# 12V_Supply.net
KiCad netlist of a schematic drawn in Altium Designer
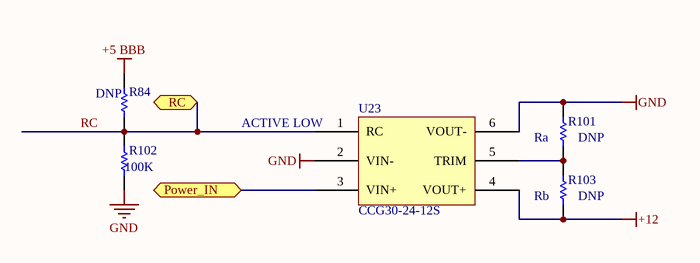
[diagram p0: 12V_Supply.SchDoc]

(export (version "E")
  (design (tool "Eeschema 10.0.6"))
  (components
    (comp (ref "R84")
      (value "DNP")
      (footprint "RESC0805(2012)_M")
      (description "RES SMD 100K OHM 1% 1/8W 0805")
      (fields
        (field (name "MANUFACTURER") "Vishay")
        (field (name "MANUFACTURER PART NUMBER") "CRCW0805100KFKEA")
      )
      (libsource (lib "Altium Content Vault") (part "CMP-1013-00017-1"))
    )
    (comp (ref "R101")
      (value "DNP")
      (footprint "RESC0805(2012)_M")
      (description "Vout = 12.05 ­ (445.7 / 63.1+Ra)")
      (libsource (lib "Altium Content Vault") (part "CMP-1013-00017-1"))
    )
    (comp (ref "R102")
      (value "RES SMD 100K OHM 1% 1/8W 0805")
      (footprint "RESC0805(2012)_M")
      (fields
        (field (name "MANUFACTURER") "Vishay")
        (field (name "MANUFACTURER PART NUMBER") "CRCW0805100KFKEA")
        (field (name "TOLERANCE") "1%")
        (field (name "RESISTANCE") "100K")
      )
      (libsource (lib "Altium Content Vault") (part "CMP-1013-00017-1"))
    )
    (comp (ref "R103")
      (value "DNP")
      (footprint "RESC0805(2012)_M")
      (description "Vout = 12.05 + (50.96 / 22+Rb)")
      (libsource (lib "Altium Content Vault") (part "CMP-1013-00017-1"))
    )
    (comp (ref "U23")
      (value "CCG30-24-12S")
      (footprint "PXB15-24WD05/N")
      (description "DC DC CONVERTER 12V 30W")
      (fields
        (field (name "MANUFACTURER") "TDK-Lambda Americas Inc.")
        (field (name "MANUFACTURER PART NUMBER") "CCG302412S")
      )
      (libsource (lib "ZLS_Schematic_lib") (part "CCG302412S"))
    )
  )
  (nets
    (net (code "1") (name "+5 BBB") (class "Default")
      (node (ref "R84") (pin "1") (pinfunction "1_1") (pintype "passive"))
    )
    (net (code "2") (name "+12") (class "Default")
      (node (ref "R103") (pin "1") (pinfunction "1_1") (pintype "passive"))
      (node (ref "U23") (pin "4") (pinfunction "VOUT+_4") (pintype "passive"))
    )
    (net (code "3") (name "/Power_IN") (class "Default")
      (node (ref "U23") (pin "3") (pinfunction "VIN+_3") (pintype "passive"))
    )
    (net (code "4") (name "/RC") (class "Default")
      (node (ref "R102") (pin "1") (pinfunction "1_1") (pintype "passive"))
      (node (ref "R84") (pin "2") (pinfunction "2_2") (pintype "passive"))
      (node (ref "U23") (pin "1") (pinfunction "RC_1") (pintype "passive"))
    )
    (net (code "5") (name "GND") (class "Default")
      (node (ref "R101") (pin "2") (pinfunction "2_2") (pintype "passive"))
      (node (ref "R102") (pin "2") (pinfunction "2_2") (pintype "passive"))
      (node (ref "U23") (pin "2") (pinfunction "VIN-_2") (pintype "passive"))
      (node (ref "U23") (pin "6") (pinfunction "VOUT-_6") (pintype "passive"))
    )
    (net (code "6") (name "Net-(U23-TRIM)") (class "Default")
      (node (ref "R101") (pin "1") (pinfunction "1_1") (pintype "passive"))
      (node (ref "R103") (pin "2") (pinfunction "2_2") (pintype "passive"))
      (node (ref "U23") (pin "5") (pinfunction "TRIM_5") (pintype "passive"))
    )
  )
)
